# FPGA_Config.net
KiCad netlist of a schematic drawn in Altium Designer
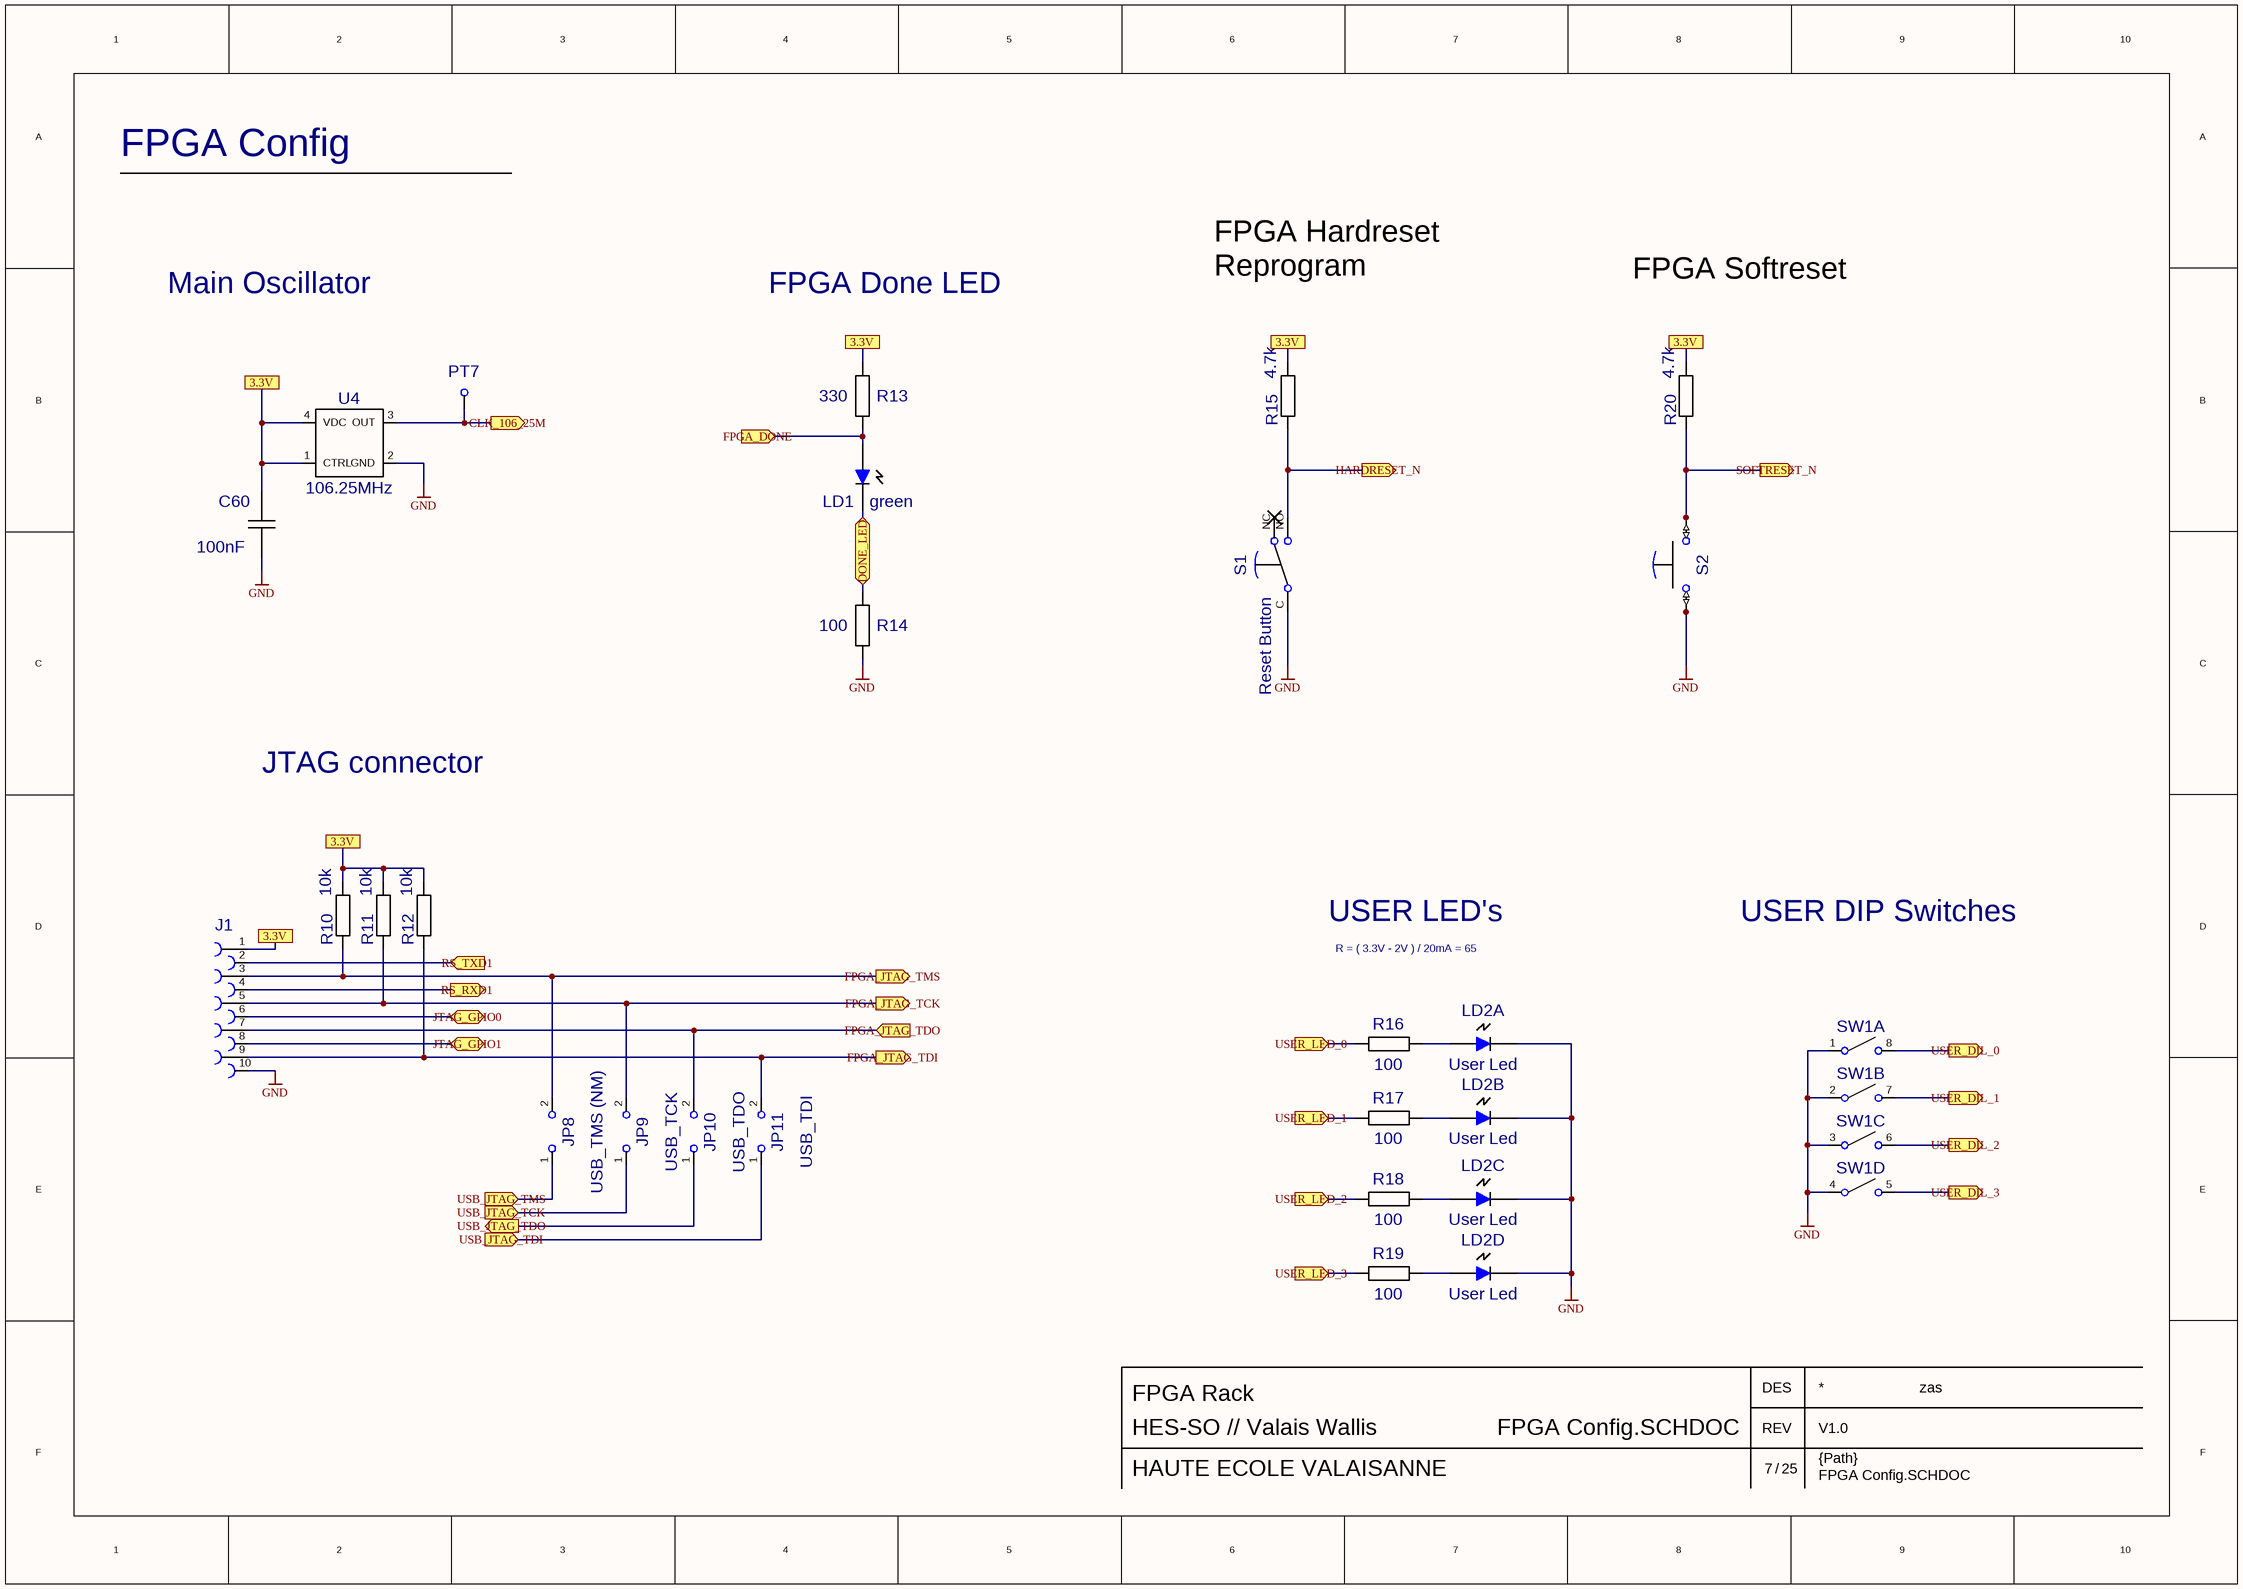
[diagram p0: FPGA Config.SCHDOC]

(export (version "E")
  (design (tool "Eeschema 10.0.6"))
  (components
    (comp (ref "C60")
      (value "100nF")
      (footprint "CC0805-MM")
      (description "Capacitor")
      (fields (field (name "Comment") "CAPS0805-MM"))
      (libsource (lib "*") (part "CAPS0805-MM"))
    )
    (comp (ref "J1")
      (value "CONNB2X5-2MM-COUDE")
      (footprint "CONN2X5-2MM-FCI-COUDE")
      (libsource (lib "*") (part "CONNB2X5-2MM-COUDE"))
    )
    (comp (ref "JP8")
      (value "USB_TMS (NM)")
      (footprint "JUMPER-SMD")
      (description "JUMPER-SMD")
      (libsource (lib "*") (part "JUMPER-SMD"))
    )
    (comp (ref "JP9")
      (value "USB_TCK")
      (footprint "JUMPER-SMD")
      (description "JUMPER-SMD")
      (libsource (lib "*") (part "JUMPER-SMD"))
    )
    (comp (ref "JP10")
      (value "USB_TDO")
      (footprint "JUMPER-SMD")
      (description "JUMPER-SMD")
      (libsource (lib "*") (part "JUMPER-SMD"))
    )
    (comp (ref "JP11")
      (value "USB_TDI")
      (footprint "JUMPER-SMD")
      (description "JUMPER-SMD")
      (libsource (lib "*") (part "JUMPER-SMD"))
    )
    (comp (ref "LD1")
      (value "green")
      (footprint "LED_SMD0805-MM")
      (description "Led smd - Stanley Distrelec N° 25 31 00")
      (fields (field (name "Comment") "LED0805-MM"))
      (libsource (lib "*") (part "LED0805-MM"))
    )
    (comp (ref "LD2")
      (value "User Led")
      (footprint "LED-569-010X-XXX")
      (description "LED Schurter - Distrelec 25 09 08...")
      (fields (field (name "Comment") "LED-569-010X-XXX"))
      (libsource (lib "*") (part "LED-569-010X-XXX"))
    )
    (comp (ref "PT7")
      (value "PTEST")
      (footprint "CONN1X1M")
      (description "PTEST_VARIANT_1")
      (libsource (lib "*") (part "PTEST"))
    )
    (comp (ref "R10")
      (value "10k")
      (footprint "RC0805-MM")
      (description "RS0805-MM")
      (libsource (lib "*") (part "RS0805-MM"))
    )
    (comp (ref "R11")
      (value "10k")
      (footprint "RC0805-MM")
      (description "RS0805-MM")
      (libsource (lib "*") (part "RS0805-MM"))
    )
    (comp (ref "R12")
      (value "10k")
      (footprint "RC0805-MM")
      (description "RS0805-MM")
      (libsource (lib "*") (part "RS0805-MM"))
    )
    (comp (ref "R13")
      (value "330")
      (footprint "RC0805-MM")
      (description "RS0805-MM")
      (libsource (lib "*") (part "RS0805-MM"))
    )
    (comp (ref "R14")
      (value "100")
      (footprint "RC0805-MM")
      (description "RS0805-MM")
      (libsource (lib "*") (part "RS0805-MM"))
    )
    (comp (ref "R15")
      (value "4.7k")
      (footprint "RC0805-MM")
      (description "RS0805-MM")
      (libsource (lib "*") (part "RS0805-MM"))
    )
    (comp (ref "R16")
      (value "100")
      (footprint "RC0805-MM")
      (description "RS0805-MM")
      (libsource (lib "*") (part "RS0805-MM"))
    )
    (comp (ref "R17")
      (value "100")
      (footprint "RC0805-MM")
      (description "RS0805-MM")
      (libsource (lib "*") (part "RS0805-MM"))
    )
    (comp (ref "R18")
      (value "100")
      (footprint "RC0805-MM")
      (description "RS0805-MM")
      (libsource (lib "*") (part "RS0805-MM"))
    )
    (comp (ref "R19")
      (value "100")
      (footprint "RC0805-MM")
      (description "RS0805-MM")
      (libsource (lib "*") (part "RS0805-MM"))
    )
    (comp (ref "R20")
      (value "4.7k")
      (footprint "RC0805-MM")
      (description "RS0805-MM")
      (libsource (lib "*") (part "RS0805-MM"))
    )
    (comp (ref "S1")
      (value "Reset Button")
      (footprint "PUSHBUTTON-03")
      (description "ITW Switches JPM 1990-0101 / Distrelec 20 15 40")
      (fields (field (name "Comment") "PUSHBUTT-SH3-01"))
      (libsource (lib "*") (part "PUSHBUTT-SH3-01"))
    )
    (comp (ref "S2")
      (value "PUSHBUTT-DTSM")
      (footprint "PUSHBUTT-DTSM")
      (description "Pushbutton NO Schurter type SMS J-leads")
      (libsource (lib "*") (part "PUSHBUTT-DTSM"))
    )
    (comp (ref "SW1")
      (value "SW-CTS-193-4MS")
      (footprint "SW-CTS-193-4MS")
      (description "Dip switch smd 4 poles - Thomas & Betts - Distrelec 21 04 21")
      (libsource (lib "*") (part "SW-CTS-193-4MS"))
    )
    (comp (ref "U4")
      (value "106.25MHz")
      (footprint "OSCILL-VX3")
      (description "Oscillator serie VX3 - Jauch - Distrelec 68 03 82 .. 68 04 00")
      (fields (field (name "Comment") "OSCILL-VX3"))
      (libsource (lib "*") (part "OSCILL-VX3"))
    )
  )
  (nets
    (net (code "2") (name "/CLK_106_25M") (class "Default")
      (node (ref "PT7") (pin "1") (pinfunction "A_1") (pintype "bidirectional"))
      (node (ref "U4") (pin "3") (pinfunction "OUT_3") (pintype "passive"))
    )
    (net (code "3") (name "/DONE_LED") (class "Default")
      (node (ref "LD1") (pin "1") (pinfunction "K_1") (pintype "passive"))
      (node (ref "R14") (pin "1") (pinfunction "1_1") (pintype "passive"))
    )
    (net (code "4") (name "/FPGA_DONE") (class "Default")
      (node (ref "LD1") (pin "2") (pinfunction "A_2") (pintype "passive"))
      (node (ref "R13") (pin "2") (pinfunction "2_2") (pintype "passive"))
    )
    (net (code "5") (name "/FPGA_JTAG_TCK") (class "Default")
      (node (ref "J1") (pin "5") (pinfunction "5_5") (pintype "bidirectional"))
      (node (ref "JP9") (pin "2") (pinfunction "2_2") (pintype "bidirectional"))
      (node (ref "R11") (pin "1") (pinfunction "1_1") (pintype "passive"))
    )
    (net (code "6") (name "/FPGA_JTAG_TDI") (class "Default")
      (node (ref "J1") (pin "9") (pinfunction "9_9") (pintype "bidirectional"))
      (node (ref "JP11") (pin "2") (pinfunction "2_2") (pintype "bidirectional"))
      (node (ref "R12") (pin "1") (pinfunction "1_1") (pintype "passive"))
    )
    (net (code "7") (name "/FPGA_JTAG_TDO") (class "Default")
      (node (ref "J1") (pin "7") (pinfunction "7_7") (pintype "bidirectional"))
      (node (ref "JP10") (pin "2") (pinfunction "2_2") (pintype "bidirectional"))
    )
    (net (code "8") (name "/FPGA_JTAG_TMS") (class "Default")
      (node (ref "J1") (pin "3") (pinfunction "3_3") (pintype "bidirectional"))
      (node (ref "JP8") (pin "2") (pinfunction "2_2") (pintype "bidirectional"))
      (node (ref "R10") (pin "1") (pinfunction "1_1") (pintype "passive"))
    )
    (net (code "9") (name "/HARDRESET_N") (class "Default")
      (node (ref "R15") (pin "1") (pinfunction "1_1") (pintype "passive"))
      (node (ref "S1") (pin "NO") (pinfunction "NO_NO") (pintype "passive"))
    )
    (net (code "10") (name "/JTAG_GPIO0") (class "Default")
      (node (ref "J1") (pin "6") (pinfunction "6_6") (pintype "bidirectional"))
    )
    (net (code "11") (name "/JTAG_GPIO1") (class "Default")
      (node (ref "J1") (pin "8") (pinfunction "8_8") (pintype "bidirectional"))
    )
    (net (code "12") (name "/RS_RXD1") (class "Default")
      (node (ref "J1") (pin "4") (pinfunction "4_4") (pintype "bidirectional"))
    )
    (net (code "13") (name "/RS_TXD1") (class "Default")
      (node (ref "J1") (pin "2") (pinfunction "2_2") (pintype "bidirectional"))
    )
    (net (code "14") (name "/SOFTRESET_N") (class "Default")
      (node (ref "R20") (pin "1") (pinfunction "1_1") (pintype "passive"))
      (node (ref "S2") (pin "3") (pinfunction "3_3") (pintype "bidirectional"))
      (node (ref "S2") (pin "4") (pinfunction "4_4") (pintype "bidirectional"))
    )
    (net (code "15") (name "/USB_JTAG_TCK") (class "Default")
      (node (ref "JP9") (pin "1") (pinfunction "1_1") (pintype "bidirectional"))
    )
    (net (code "16") (name "/USB_JTAG_TDI") (class "Default")
      (node (ref "JP11") (pin "1") (pinfunction "1_1") (pintype "bidirectional"))
    )
    (net (code "17") (name "/USB_JTAG_TDO") (class "Default")
      (node (ref "JP10") (pin "1") (pinfunction "1_1") (pintype "bidirectional"))
    )
    (net (code "18") (name "/USB_JTAG_TMS") (class "Default")
      (node (ref "JP8") (pin "1") (pinfunction "1_1") (pintype "bidirectional"))
    )
    (net (code "19") (name "/USER_DIL_0") (class "Default")
      (node (ref "SW1") (pin "8") (pintype "bidirectional"))
    )
    (net (code "20") (name "/USER_DIL_1") (class "Default")
      (node (ref "SW1") (pin "7") (pintype "bidirectional"))
    )
    (net (code "21") (name "/USER_DIL_2") (class "Default")
      (node (ref "SW1") (pin "6") (pintype "bidirectional"))
    )
    (net (code "22") (name "/USER_DIL_3") (class "Default")
      (node (ref "SW1") (pin "5") (pintype "bidirectional"))
    )
    (net (code "23") (name "/USER_LED_0") (class "Default")
      (node (ref "R16") (pin "1") (pinfunction "1_1") (pintype "passive"))
    )
    (net (code "24") (name "/USER_LED_1") (class "Default")
      (node (ref "R17") (pin "1") (pinfunction "1_1") (pintype "passive"))
    )
    (net (code "25") (name "/USER_LED_2") (class "Default")
      (node (ref "R18") (pin "1") (pinfunction "1_1") (pintype "passive"))
    )
    (net (code "26") (name "/USER_LED_3") (class "Default")
      (node (ref "R19") (pin "1") (pinfunction "1_1") (pintype "passive"))
    )
    (net (code "27") (name "GND") (class "Default")
      (node (ref "C60") (pin "1") (pinfunction "1_1") (pintype "passive"))
      (node (ref "J1") (pin "10") (pinfunction "10_10") (pintype "bidirectional"))
      (node (ref "LD2") (pin "2") (pinfunction "-_2") (pintype "passive"))
      (node (ref "LD2") (pin "4") (pinfunction "-_4") (pintype "passive"))
      (node (ref "LD2") (pin "6") (pinfunction "-_6") (pintype "passive"))
      (node (ref "LD2") (pin "8") (pinfunction "-_8") (pintype "passive"))
      (node (ref "R14") (pin "2") (pinfunction "2_2") (pintype "passive"))
      (node (ref "S1") (pin "C") (pinfunction "C_C") (pintype "passive"))
      (node (ref "S2") (pin "1") (pinfunction "1_1") (pintype "bidirectional"))
      (node (ref "S2") (pin "2") (pinfunction "2_2") (pintype "bidirectional"))
      (node (ref "SW1") (pin "1") (pintype "bidirectional"))
      (node (ref "SW1") (pin "2") (pintype "bidirectional"))
      (node (ref "SW1") (pin "3") (pintype "bidirectional"))
      (node (ref "SW1") (pin "4") (pintype "bidirectional"))
      (node (ref "U4") (pin "2") (pinfunction "GND_2") (pintype "passive"))
    )
    (net (code "28") (name "Net-(LD2A-+)") (class "Default")
      (node (ref "LD2") (pin "1") (pinfunction "+_1") (pintype "passive"))
      (node (ref "R16") (pin "2") (pinfunction "2_2") (pintype "passive"))
    )
    (net (code "29") (name "Net-(LD2B-+)") (class "Default")
      (node (ref "LD2") (pin "3") (pinfunction "+_3") (pintype "passive"))
      (node (ref "R17") (pin "2") (pinfunction "2_2") (pintype "passive"))
    )
    (net (code "30") (name "Net-(LD2C-+)") (class "Default")
      (node (ref "LD2") (pin "5") (pinfunction "+_5") (pintype "passive"))
      (node (ref "R18") (pin "2") (pinfunction "2_2") (pintype "passive"))
    )
    (net (code "31") (name "Net-(LD2D-+)") (class "Default")
      (node (ref "LD2") (pin "7") (pinfunction "+_7") (pintype "passive"))
      (node (ref "R19") (pin "2") (pinfunction "2_2") (pintype "passive"))
    )
    (net (code "32") (name "Net-(R10-Pad2)") (class "Default")
      (node (ref "R10") (pin "2") (pinfunction "2_2") (pintype "passive"))
      (node (ref "R11") (pin "2") (pinfunction "2_2") (pintype "passive"))
      (node (ref "R12") (pin "2") (pinfunction "2_2") (pintype "passive"))
    )
    (net (code "33") (name "Net-(U4-CTRL)") (class "Default")
      (node (ref "C60") (pin "2") (pinfunction "2_2") (pintype "passive"))
      (node (ref "U4") (pin "1") (pinfunction "CTRL_1") (pintype "passive"))
      (node (ref "U4") (pin "4") (pinfunction "VDC_4") (pintype "passive"))
    )
    (net (code "34") (name "unconnected-(J1-Pad1)") (class "Default")
      (node (ref "J1") (pin "1") (pinfunction "1_1") (pintype "bidirectional"))
    )
    (net (code "35") (name "unconnected-(R13-Pad1)") (class "Default")
      (node (ref "R13") (pin "1") (pinfunction "1_1") (pintype "passive"))
    )
    (net (code "36") (name "unconnected-(R15-Pad2)") (class "Default")
      (node (ref "R15") (pin "2") (pinfunction "2_2") (pintype "passive"))
    )
    (net (code "37") (name "unconnected-(R20-Pad2)") (class "Default")
      (node (ref "R20") (pin "2") (pinfunction "2_2") (pintype "passive"))
    )
    (net (code "38") (name "unconnected-(S1-PadNC)") (class "Default")
      (node (ref "S1") (pin "NC") (pinfunction "NC_NC") (pintype "passive"))
    )
  )
)
